# electrotactile_fanout.net
KiCad netlist of a schematic drawn in EAGLE
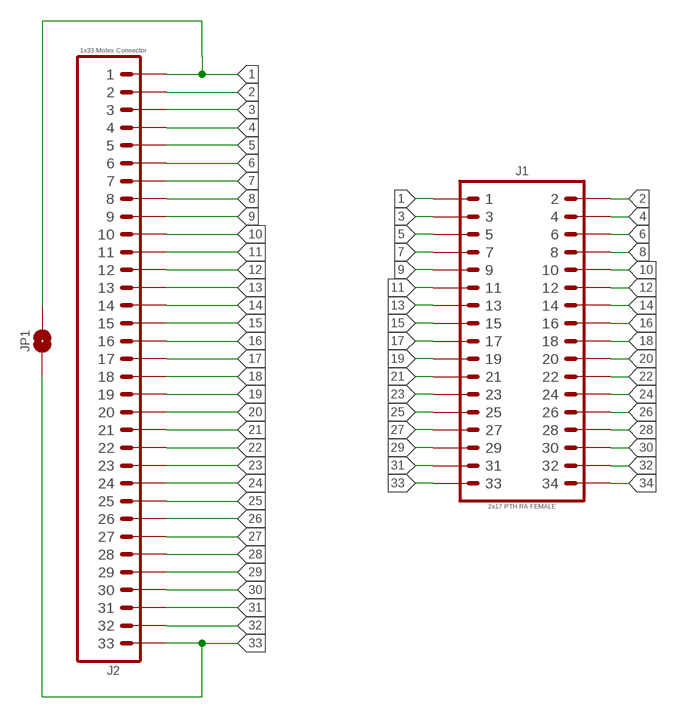
[diagram p0: schematic, sheet 1]

(export (version "E")
  (design (tool "Eeschema 10.0.6"))
  (components
    (comp (ref "J1")
      (value "2x17 PTH RA FEMALE")
      (footprint "eagle-import:2X17-RA-FEMALE")
      (fields (field (name "MFR") "Samtec Inc.") (field (name "MPN") "SSQ-117-02-T-D-RA"))
      (libsource (lib "eagle-import") (part "2X17_PTH_RA-FEMALE"))
    )
    (comp (ref "J2")
      (value "1x33 Molex Connector")
      (footprint "eagle-import:_MOLEX-5025983393_FPC_PITCH-0.3MM")
      (fields (field (name "MFR") "Molex, LLC") (field (name "MPN") "5025983393"))
      (libsource (lib "eagle-import") (part "1X33_MOLEX_FPC_FPC_RIBBON-CABLE"))
    )
    (comp (ref "JP1")
      (value "JUMPER_SMD_2-PAD_NO_SILK")
      (footprint "eagle-import:SMT-JUMPER_2_NO_SILK")
      (libsource (lib "eagle-import") (part "JUMPER_SMD_2-PAD_NO_SILK"))
    )
  )
  (nets
    (net (code "1") (name "1") (class "Default")
      (node (ref "J1") (pin "1") (pinfunction "1_1") (pintype "bidirectional"))
      (node (ref "J2") (pin "P$1") (pinfunction "1_P$1") (pintype "passive"))
      (node (ref "JP1") (pin "2") (pinfunction "2_2") (pintype "passive"))
    )
    (net (code "2") (name "2") (class "Default")
      (node (ref "J1") (pin "2") (pinfunction "2_2") (pintype "bidirectional"))
      (node (ref "J2") (pin "P$2") (pinfunction "2_P$2") (pintype "passive"))
    )
    (net (code "3") (name "3") (class "Default")
      (node (ref "J1") (pin "3") (pinfunction "3_3") (pintype "bidirectional"))
      (node (ref "J2") (pin "P$3") (pinfunction "3_P$3") (pintype "passive"))
    )
    (net (code "4") (name "4") (class "Default")
      (node (ref "J1") (pin "4") (pinfunction "4_4") (pintype "bidirectional"))
      (node (ref "J2") (pin "P$4") (pinfunction "4_P$4") (pintype "passive"))
    )
    (net (code "5") (name "5") (class "Default")
      (node (ref "J1") (pin "5") (pinfunction "5_5") (pintype "bidirectional"))
      (node (ref "J2") (pin "P$5") (pinfunction "5_P$5") (pintype "passive"))
    )
    (net (code "6") (name "6") (class "Default")
      (node (ref "J1") (pin "6") (pinfunction "6_6") (pintype "bidirectional"))
      (node (ref "J2") (pin "P$6") (pinfunction "6_P$6") (pintype "passive"))
    )
    (net (code "7") (name "7") (class "Default")
      (node (ref "J1") (pin "7") (pinfunction "7_7") (pintype "bidirectional"))
      (node (ref "J2") (pin "P$7") (pinfunction "7_P$7") (pintype "passive"))
    )
    (net (code "8") (name "8") (class "Default")
      (node (ref "J1") (pin "8") (pinfunction "8_8") (pintype "bidirectional"))
      (node (ref "J2") (pin "P$8") (pinfunction "8_P$8") (pintype "passive"))
    )
    (net (code "9") (name "9") (class "Default")
      (node (ref "J1") (pin "9") (pinfunction "9_9") (pintype "bidirectional"))
      (node (ref "J2") (pin "P$9") (pinfunction "9_P$9") (pintype "passive"))
    )
    (net (code "10") (name "10") (class "Default")
      (node (ref "J1") (pin "10") (pinfunction "10_10") (pintype "bidirectional"))
      (node (ref "J2") (pin "P$10") (pinfunction "10_P$10") (pintype "passive"))
    )
    (net (code "11") (name "11") (class "Default")
      (node (ref "J1") (pin "11") (pinfunction "11_11") (pintype "bidirectional"))
      (node (ref "J2") (pin "P$11") (pinfunction "11_P$11") (pintype "passive"))
    )
    (net (code "12") (name "12") (class "Default")
      (node (ref "J1") (pin "12") (pinfunction "12_12") (pintype "bidirectional"))
      (node (ref "J2") (pin "P$12") (pinfunction "12_P$12") (pintype "passive"))
    )
    (net (code "13") (name "13") (class "Default")
      (node (ref "J1") (pin "13") (pinfunction "13_13") (pintype "bidirectional"))
      (node (ref "J2") (pin "P$13") (pinfunction "13_P$13") (pintype "passive"))
    )
    (net (code "14") (name "14") (class "Default")
      (node (ref "J1") (pin "14") (pinfunction "14_14") (pintype "bidirectional"))
      (node (ref "J2") (pin "P$14") (pinfunction "14_P$14") (pintype "passive"))
    )
    (net (code "15") (name "15") (class "Default")
      (node (ref "J1") (pin "15") (pinfunction "15_15") (pintype "bidirectional"))
      (node (ref "J2") (pin "P$15") (pinfunction "15_P$15") (pintype "passive"))
    )
    (net (code "16") (name "16") (class "Default")
      (node (ref "J1") (pin "16") (pinfunction "16_16") (pintype "bidirectional"))
      (node (ref "J2") (pin "P$16") (pinfunction "16_P$16") (pintype "passive"))
    )
    (net (code "17") (name "17") (class "Default")
      (node (ref "J1") (pin "17") (pinfunction "17_17") (pintype "bidirectional"))
      (node (ref "J2") (pin "P$17") (pinfunction "17_P$17") (pintype "passive"))
    )
    (net (code "18") (name "18") (class "Default")
      (node (ref "J1") (pin "18") (pinfunction "18_18") (pintype "bidirectional"))
      (node (ref "J2") (pin "P$18") (pinfunction "18_P$18") (pintype "passive"))
    )
    (net (code "19") (name "19") (class "Default")
      (node (ref "J1") (pin "19") (pinfunction "19_19") (pintype "bidirectional"))
      (node (ref "J2") (pin "P$19") (pinfunction "19_P$19") (pintype "passive"))
    )
    (net (code "20") (name "20") (class "Default")
      (node (ref "J1") (pin "20") (pinfunction "20_20") (pintype "bidirectional"))
      (node (ref "J2") (pin "P$20") (pinfunction "20_P$20") (pintype "passive"))
    )
    (net (code "21") (name "21") (class "Default")
      (node (ref "J1") (pin "21") (pinfunction "21_21") (pintype "bidirectional"))
      (node (ref "J2") (pin "P$21") (pinfunction "21_P$21") (pintype "passive"))
    )
    (net (code "22") (name "22") (class "Default")
      (node (ref "J1") (pin "22") (pinfunction "22_22") (pintype "bidirectional"))
      (node (ref "J2") (pin "P$22") (pinfunction "22_P$22") (pintype "passive"))
    )
    (net (code "23") (name "23") (class "Default")
      (node (ref "J1") (pin "23") (pinfunction "23_23") (pintype "bidirectional"))
      (node (ref "J2") (pin "P$23") (pinfunction "23_P$23") (pintype "passive"))
    )
    (net (code "24") (name "24") (class "Default")
      (node (ref "J1") (pin "24") (pinfunction "24_24") (pintype "bidirectional"))
      (node (ref "J2") (pin "P$24") (pinfunction "24_P$24") (pintype "passive"))
    )
    (net (code "25") (name "25") (class "Default")
      (node (ref "J1") (pin "25") (pinfunction "25_25") (pintype "bidirectional"))
      (node (ref "J2") (pin "P$25") (pinfunction "25_P$25") (pintype "passive"))
    )
    (net (code "26") (name "26") (class "Default")
      (node (ref "J1") (pin "26") (pinfunction "26_26") (pintype "bidirectional"))
      (node (ref "J2") (pin "P$26") (pinfunction "26_P$26") (pintype "passive"))
    )
    (net (code "27") (name "27") (class "Default")
      (node (ref "J1") (pin "27") (pinfunction "27_27") (pintype "bidirectional"))
      (node (ref "J2") (pin "P$27") (pinfunction "27_P$27") (pintype "passive"))
    )
    (net (code "28") (name "28") (class "Default")
      (node (ref "J1") (pin "28") (pinfunction "28_28") (pintype "bidirectional"))
      (node (ref "J2") (pin "P$28") (pinfunction "28_P$28") (pintype "passive"))
    )
    (net (code "29") (name "29") (class "Default")
      (node (ref "J1") (pin "29") (pinfunction "29_29") (pintype "bidirectional"))
      (node (ref "J2") (pin "P$29") (pinfunction "29_P$29") (pintype "passive"))
    )
    (net (code "30") (name "30") (class "Default")
      (node (ref "J1") (pin "30") (pinfunction "30_30") (pintype "bidirectional"))
      (node (ref "J2") (pin "P$30") (pinfunction "30_P$30") (pintype "passive"))
    )
    (net (code "31") (name "31") (class "Default")
      (node (ref "J1") (pin "31") (pinfunction "31_31") (pintype "bidirectional"))
      (node (ref "J2") (pin "P$31") (pinfunction "31_P$31") (pintype "passive"))
    )
    (net (code "32") (name "32") (class "Default")
      (node (ref "J1") (pin "32") (pinfunction "32_32") (pintype "bidirectional"))
      (node (ref "J2") (pin "P$32") (pinfunction "32_P$32") (pintype "passive"))
    )
    (net (code "33") (name "33") (class "Default")
      (node (ref "J1") (pin "33") (pinfunction "33_33") (pintype "bidirectional"))
      (node (ref "J2") (pin "P$33") (pinfunction "33_P$33") (pintype "passive"))
      (node (ref "JP1") (pin "1") (pinfunction "1_1") (pintype "passive"))
    )
    (net (code "34") (name "34") (class "Default")
      (node (ref "J1") (pin "34") (pinfunction "34_34") (pintype "bidirectional"))
    )
  )
)
